# DC309A_CLKGen.net
KiCad netlist of a schematic drawn in Altium Designer
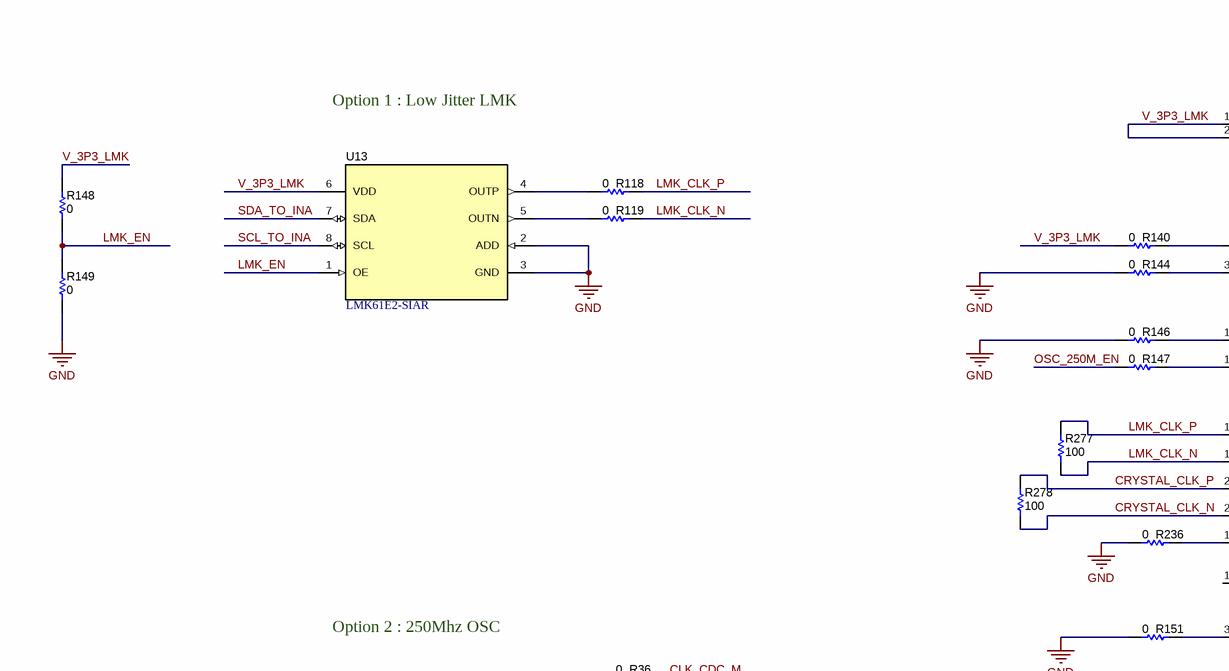
[diagram p0: DC309A_CLKGen.SchDoc, top left]
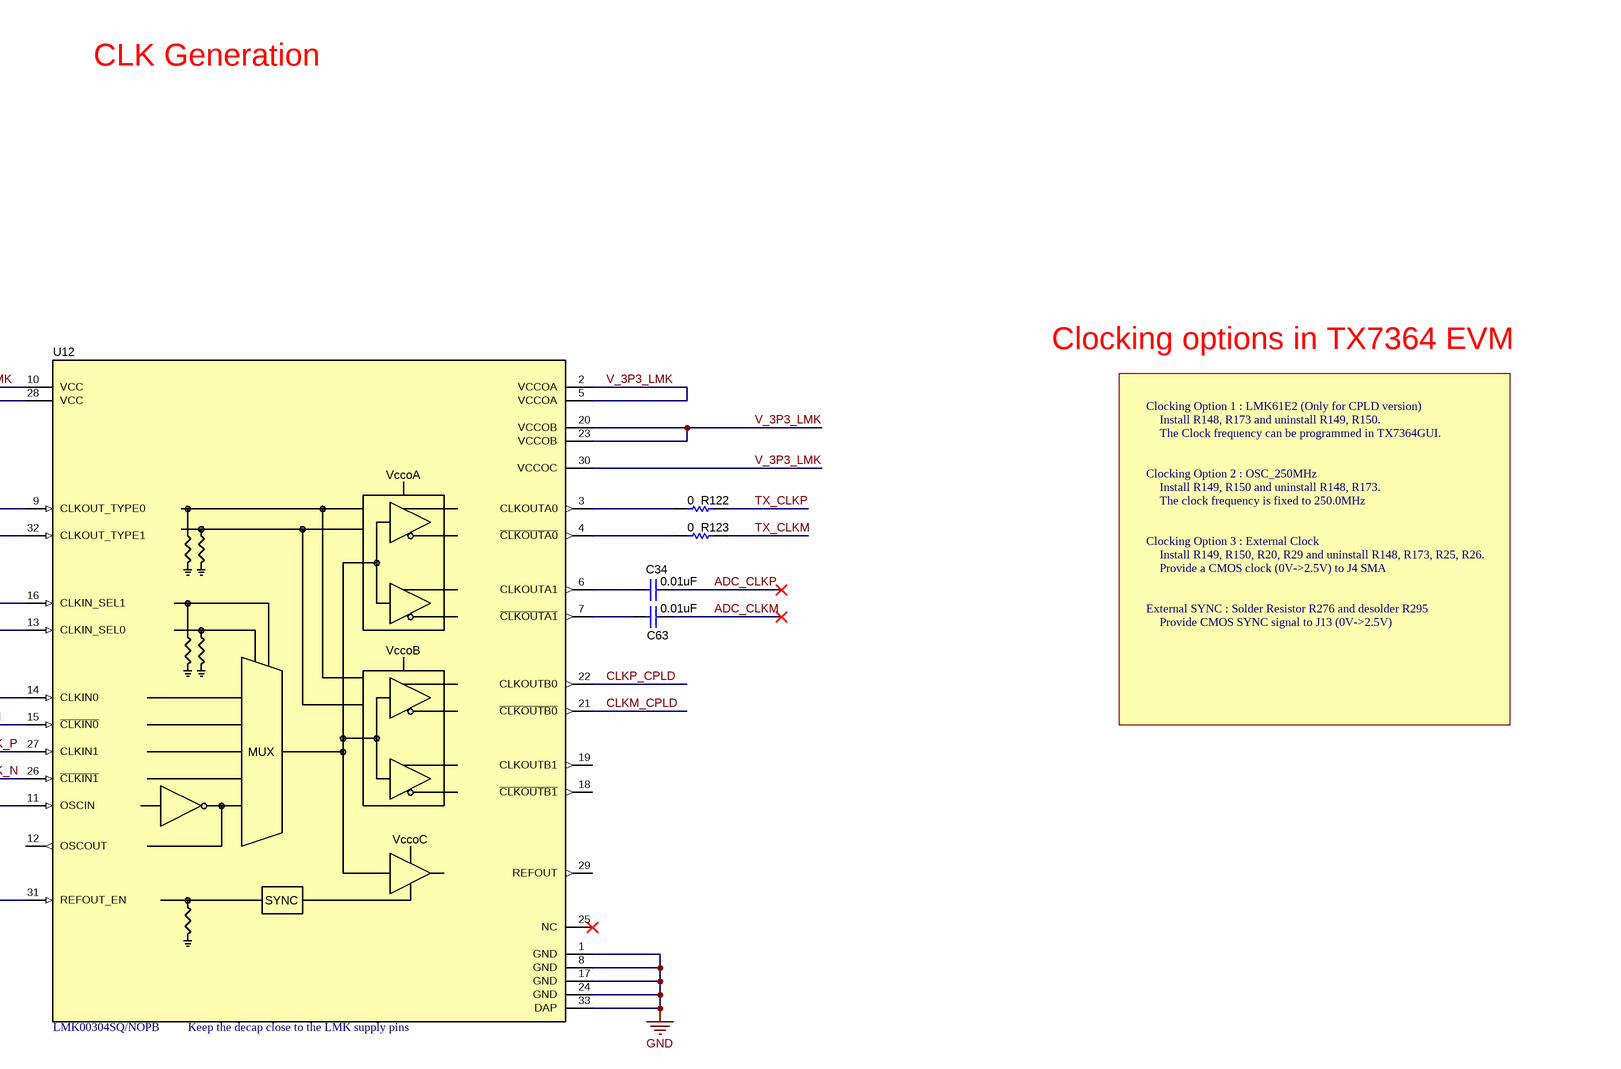
[diagram p1: DC309A_CLKGen.SchDoc, top right]
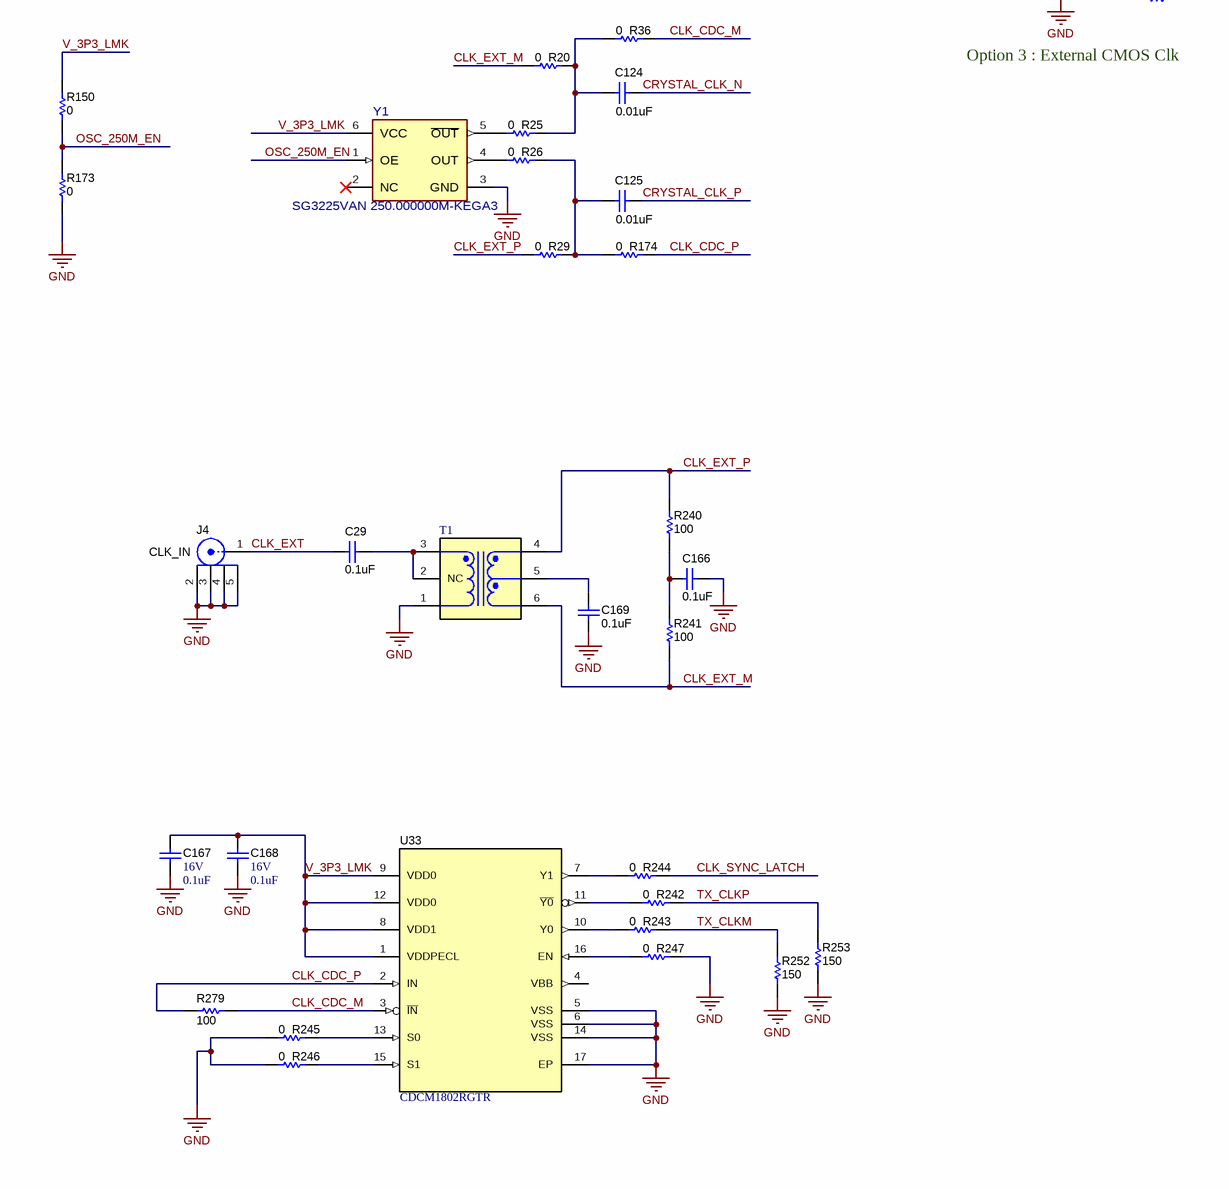
[diagram p2: DC309A_CLKGen.SchDoc, bottom left]
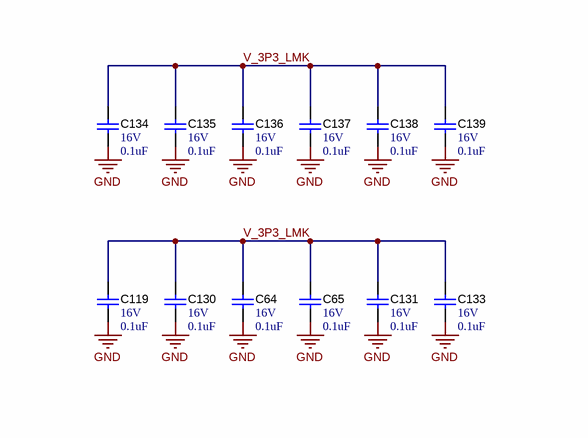
[diagram p3: DC309A_CLKGen.SchDoc, bottom right]

(export (version "E")
  (design (tool "Eeschema 10.0.6"))
  (components
    (comp (ref "C29")
      (value "Capacitor")
      (footprint "0402")
      (description "CAP, CERM, 0.1 uF, 6.3 V, +/- 10%, X5R, 0402")
      (fields
        (field (name "PARTNUMBER") "C1005X5R0J104K050BA")
        (field (name "VALUEDISPLAYED") "0.1uF")
        (field (name "MANUFACTURER") "TDK")
        (field (name "PUBLISHER") "Texas Instruments")
      )
      (libsource (lib "Altium Vault - TI") (part "Capacitor"))
    )
    (comp (ref "C34")
      (value "520L103KT16T")
      (footprint "0402_065")
      (description "CAP, CERM, 0.01 uF, 16 V, +/- 10%, X7R, 0402")
      (fields
        (field (name "MANUFACTURER") "AT Ceramics")
        (field (name "VALUEDISPLAYED") "0.01uF")
        (field (name "PUBLISHER") "Texas Instruments")
      )
      (libsource (lib "Altium Vault - TI") (part "CMP-0006210-2"))
    )
    (comp (ref "C63")
      (value "520L103KT16T")
      (footprint "0402_065")
      (description "CAP, CERM, 0.01 uF, 16 V, +/- 10%, X7R, 0402")
      (fields
        (field (name "MANUFACTURER") "AT Ceramics")
        (field (name "VALUEDISPLAYED") "0.01uF")
        (field (name "PUBLISHER") "Texas Instruments")
      )
      (libsource (lib "Altium Vault - TI") (part "CMP-0006210-2"))
    )
    (comp (ref "C64")
      (value "0402YC104KAT2A")
      (footprint "0402")
      (description "CAP, CERM, 0.1 uF, 16 V, +/- 10%, X7R, 0402")
      (fields
        (field (name "MANUFACTURER") "AVX")
        (field (name "VDC_V") "16V")
        (field (name "VALUEDISPLAYED") "0.1uF")
        (field (name "PUBLISHER") "Texas Instruments")
      )
      (libsource (lib "Altium Vault - TI") (part "Capacitor"))
    )
    (comp (ref "C65")
      (value "0402YC104KAT2A")
      (footprint "0402")
      (description "CAP, CERM, 0.1 uF, 16 V, +/- 10%, X7R, 0402")
      (fields
        (field (name "MANUFACTURER") "AVX")
        (field (name "VDC_V") "16V")
        (field (name "VALUEDISPLAYED") "0.1uF")
        (field (name "PUBLISHER") "Texas Instruments")
      )
      (libsource (lib "Altium Vault - TI") (part "Capacitor"))
    )
    (comp (ref "C119")
      (value "0402YC104KAT2A")
      (footprint "0402")
      (description "CAP, CERM, 0.1 uF, 16 V, +/- 10%, X7R, 0402")
      (fields
        (field (name "MANUFACTURER") "AVX")
        (field (name "VDC_V") "16V")
        (field (name "VALUEDISPLAYED") "0.1uF")
        (field (name "PUBLISHER") "Texas Instruments")
      )
      (libsource (lib "Altium Vault - TI") (part "Capacitor"))
    )
    (comp (ref "C124")
      (value "520L103KT16T")
      (footprint "0402_065")
      (description "CAP, CERM, 0.01 uF, 16 V, +/- 10%, X7R, 0402")
      (fields
        (field (name "MANUFACTURER") "AT Ceramics")
        (field (name "VALUEDISPLAYED") "0.01uF")
        (field (name "PUBLISHER") "Texas Instruments")
      )
      (libsource (lib "Altium Vault - TI") (part "CMP-0006210-2"))
    )
    (comp (ref "C125")
      (value "520L103KT16T")
      (footprint "0402_065")
      (description "CAP, CERM, 0.01 uF, 16 V, +/- 10%, X7R, 0402")
      (fields
        (field (name "MANUFACTURER") "AT Ceramics")
        (field (name "VALUEDISPLAYED") "0.01uF")
        (field (name "PUBLISHER") "Texas Instruments")
      )
      (libsource (lib "Altium Vault - TI") (part "CMP-0006210-2"))
    )
    (comp (ref "C130")
      (value "0402YC104KAT2A")
      (footprint "0402")
      (description "CAP, CERM, 0.1 uF, 16 V, +/- 10%, X7R, 0402")
      (fields
        (field (name "MANUFACTURER") "AVX")
        (field (name "VDC_V") "16V")
        (field (name "VALUEDISPLAYED") "0.1uF")
        (field (name "PUBLISHER") "Texas Instruments")
      )
      (libsource (lib "Altium Vault - TI") (part "Capacitor"))
    )
    (comp (ref "C131")
      (value "0402YC104KAT2A")
      (footprint "0402")
      (description "CAP, CERM, 0.1 uF, 16 V, +/- 10%, X7R, 0402")
      (fields
        (field (name "MANUFACTURER") "AVX")
        (field (name "VDC_V") "16V")
        (field (name "VALUEDISPLAYED") "0.1uF")
        (field (name "PUBLISHER") "Texas Instruments")
      )
      (libsource (lib "Altium Vault - TI") (part "Capacitor"))
    )
    (comp (ref "C133")
      (value "0402YC104KAT2A")
      (footprint "0402")
      (description "CAP, CERM, 0.1 uF, 16 V, +/- 10%, X7R, 0402")
      (fields
        (field (name "MANUFACTURER") "AVX")
        (field (name "VDC_V") "16V")
        (field (name "VALUEDISPLAYED") "0.1uF")
        (field (name "PUBLISHER") "Texas Instruments")
      )
      (libsource (lib "Altium Vault - TI") (part "Capacitor"))
    )
    (comp (ref "C134")
      (value "0402YC104KAT2A")
      (footprint "0402")
      (description "CAP, CERM, 0.1 uF, 16 V, +/- 10%, X7R, 0402")
      (fields
        (field (name "MANUFACTURER") "AVX")
        (field (name "VDC_V") "16V")
        (field (name "VALUEDISPLAYED") "0.1uF")
        (field (name "PUBLISHER") "Texas Instruments")
      )
      (libsource (lib "Altium Vault - TI") (part "Capacitor"))
    )
    (comp (ref "C135")
      (value "0402YC104KAT2A")
      (footprint "0402")
      (description "CAP, CERM, 0.1 uF, 16 V, +/- 10%, X7R, 0402")
      (fields
        (field (name "MANUFACTURER") "AVX")
        (field (name "VDC_V") "16V")
        (field (name "VALUEDISPLAYED") "0.1uF")
        (field (name "PUBLISHER") "Texas Instruments")
      )
      (libsource (lib "Altium Vault - TI") (part "Capacitor"))
    )
    (comp (ref "C136")
      (value "0402YC104KAT2A")
      (footprint "0402")
      (description "CAP, CERM, 0.1 uF, 16 V, +/- 10%, X7R, 0402")
      (fields
        (field (name "MANUFACTURER") "AVX")
        (field (name "VDC_V") "16V")
        (field (name "VALUEDISPLAYED") "0.1uF")
        (field (name "PUBLISHER") "Texas Instruments")
      )
      (libsource (lib "Altium Vault - TI") (part "Capacitor"))
    )
    (comp (ref "C137")
      (value "0402YC104KAT2A")
      (footprint "0402")
      (description "CAP, CERM, 0.1 uF, 16 V, +/- 10%, X7R, 0402")
      (fields
        (field (name "MANUFACTURER") "AVX")
        (field (name "VDC_V") "16V")
        (field (name "VALUEDISPLAYED") "0.1uF")
        (field (name "PUBLISHER") "Texas Instruments")
      )
      (libsource (lib "Altium Vault - TI") (part "Capacitor"))
    )
    (comp (ref "C138")
      (value "0402YC104KAT2A")
      (footprint "0402")
      (description "CAP, CERM, 0.1 uF, 16 V, +/- 10%, X7R, 0402")
      (fields
        (field (name "MANUFACTURER") "AVX")
        (field (name "VDC_V") "16V")
        (field (name "VALUEDISPLAYED") "0.1uF")
        (field (name "PUBLISHER") "Texas Instruments")
      )
      (libsource (lib "Altium Vault - TI") (part "Capacitor"))
    )
    (comp (ref "C139")
      (value "0402YC104KAT2A")
      (footprint "0402")
      (description "CAP, CERM, 0.1 uF, 16 V, +/- 10%, X7R, 0402")
      (fields
        (field (name "MANUFACTURER") "AVX")
        (field (name "VDC_V") "16V")
        (field (name "VALUEDISPLAYED") "0.1uF")
        (field (name "PUBLISHER") "Texas Instruments")
      )
      (libsource (lib "Altium Vault - TI") (part "Capacitor"))
    )
    (comp (ref "C166")
      (value "Capacitor")
      (footprint "0402")
      (description "CAP, CERM, 0.1 uF, 6.3 V, +/- 10%, X5R, 0402")
      (fields
        (field (name "PARTNUMBER") "C1005X5R0J104K050BA")
        (field (name "VALUEDISPLAYED") "0.1uF")
        (field (name "MANUFACTURER") "TDK")
        (field (name "PUBLISHER") "Texas Instruments")
      )
      (libsource (lib "Altium Vault - TI") (part "Capacitor"))
    )
    (comp (ref "C167")
      (value "0402YC104KAT2A")
      (footprint "0402")
      (description "CAP, CERM, 0.1 uF, 16 V, +/- 10%, X7R, 0402")
      (fields
        (field (name "MANUFACTURER") "AVX")
        (field (name "VDC_V") "16V")
        (field (name "VALUEDISPLAYED") "0.1uF")
        (field (name "PUBLISHER") "Texas Instruments")
      )
      (libsource (lib "Altium Vault - TI") (part "Capacitor"))
    )
    (comp (ref "C168")
      (value "0402YC104KAT2A")
      (footprint "0402")
      (description "CAP, CERM, 0.1 uF, 16 V, +/- 10%, X7R, 0402")
      (fields
        (field (name "MANUFACTURER") "AVX")
        (field (name "VDC_V") "16V")
        (field (name "VALUEDISPLAYED") "0.1uF")
        (field (name "PUBLISHER") "Texas Instruments")
      )
      (libsource (lib "Altium Vault - TI") (part "Capacitor"))
    )
    (comp (ref "C169")
      (value "Capacitor")
      (footprint "0402")
      (description "CAP, CERM, 0.1 uF, 6.3 V, +/- 10%, X5R, 0402")
      (fields
        (field (name "PARTNUMBER") "C1005X5R0J104K050BA")
        (field (name "VALUEDISPLAYED") "0.1uF")
        (field (name "MANUFACTURER") "TDK")
        (field (name "PUBLISHER") "Texas Instruments")
      )
      (libsource (lib "Altium Vault - TI") (part "Capacitor"))
    )
    (comp (ref "J4")
      (value "901-144-8RFX")
      (footprint "AMPHENOL_901-144-8RFX")
      (description "SMA Straight Jack, Gold, 50 Ohm, TH")
      (fields (field (name "MANUFACTURER") "Amphenol RF") (field (name "PUBLISHER") "Texas Instruments"))
      (libsource (lib "Altium Vault - TI") (part "SMA_Contact1_GND2345"))
    )
    (comp (ref "R20")
      (value "Resistor")
      (footprint "0402")
      (description "RES, 0, 5%, 0.1 W, AEC-Q200 Grade 0, 0402")
      (fields
        (field (name "PARTNUMBER") "ERJ-2GE0R00X")
        (field (name "MANUFACTURER") "Panasonic")
        (field (name "RES_OHM") "0")
      )
      (libsource (lib "Altium Vault - TI") (part "CMP-0026992-3"))
    )
    (comp (ref "R25")
      (value "Resistor")
      (footprint "0402")
      (description "RES, 0, 5%, 0.1 W, AEC-Q200 Grade 0, 0402")
      (fields
        (field (name "PARTNUMBER") "ERJ-2GE0R00X")
        (field (name "MANUFACTURER") "Panasonic")
        (field (name "RES_OHM") "0")
      )
      (libsource (lib "Altium Vault - TI") (part "CMP-0026992-3"))
    )
    (comp (ref "R26")
      (value "Resistor")
      (footprint "0402")
      (description "RES, 0, 5%, 0.1 W, AEC-Q200 Grade 0, 0402")
      (fields
        (field (name "PARTNUMBER") "ERJ-2GE0R00X")
        (field (name "MANUFACTURER") "Panasonic")
        (field (name "RES_OHM") "0")
      )
      (libsource (lib "Altium Vault - TI") (part "CMP-0026992-3"))
    )
    (comp (ref "R29")
      (value "Resistor")
      (footprint "0402")
      (description "RES, 0, 5%, 0.1 W, AEC-Q200 Grade 0, 0402")
      (fields
        (field (name "PARTNUMBER") "ERJ-2GE0R00X")
        (field (name "MANUFACTURER") "Panasonic")
        (field (name "RES_OHM") "0")
      )
      (libsource (lib "Altium Vault - TI") (part "CMP-0026992-3"))
    )
    (comp (ref "R36")
      (value "Resistor")
      (footprint "0402")
      (description "RES, 0, 5%, 0.1 W, AEC-Q200 Grade 0, 0402")
      (fields
        (field (name "PARTNUMBER") "ERJ-2GE0R00X")
        (field (name "MANUFACTURER") "Panasonic")
        (field (name "RES_OHM") "0")
      )
      (libsource (lib "Altium Vault - TI") (part "CMP-0026992-3"))
    )
    (comp (ref "R118")
      (value "Resistor")
      (footprint "0402")
      (description "RES, 0, 5%, 0.1 W, AEC-Q200 Grade 0, 0402")
      (fields
        (field (name "PARTNUMBER") "ERJ-2GE0R00X")
        (field (name "MANUFACTURER") "Panasonic")
        (field (name "RES_OHM") "0")
      )
      (libsource (lib "Altium Vault - TI") (part "CMP-0026992-3"))
    )
    (comp (ref "R119")
      (value "Resistor")
      (footprint "0402")
      (description "RES, 0, 5%, 0.1 W, AEC-Q200 Grade 0, 0402")
      (fields
        (field (name "PARTNUMBER") "ERJ-2GE0R00X")
        (field (name "MANUFACTURER") "Panasonic")
        (field (name "RES_OHM") "0")
      )
      (libsource (lib "Altium Vault - TI") (part "CMP-0026992-3"))
    )
    (comp (ref "R122")
      (value "Resistor")
      (footprint "0402")
      (description "RES, 0, 5%, 0.1 W, AEC-Q200 Grade 0, 0402")
      (fields
        (field (name "PARTNUMBER") "ERJ-2GE0R00X")
        (field (name "MANUFACTURER") "Panasonic")
        (field (name "RES_OHM") "0")
      )
      (libsource (lib "Altium Vault - TI") (part "CMP-0026992-3"))
    )
    (comp (ref "R123")
      (value "Resistor")
      (footprint "0402")
      (description "RES, 0, 5%, 0.1 W, AEC-Q200 Grade 0, 0402")
      (fields
        (field (name "PARTNUMBER") "ERJ-2GE0R00X")
        (field (name "MANUFACTURER") "Panasonic")
        (field (name "RES_OHM") "0")
      )
      (libsource (lib "Altium Vault - TI") (part "CMP-0026992-3"))
    )
    (comp (ref "R140")
      (value "Resistor")
      (footprint "0402")
      (description "RES, 0, 5%, 0.1 W, AEC-Q200 Grade 0, 0402")
      (fields
        (field (name "PARTNUMBER") "ERJ-2GE0R00X")
        (field (name "MANUFACTURER") "Panasonic")
        (field (name "RES_OHM") "0")
      )
      (libsource (lib "Altium Vault - TI") (part "CMP-0026992-3"))
    )
    (comp (ref "R144")
      (value "Resistor")
      (footprint "0402")
      (description "RES, 0, 5%, 0.1 W, AEC-Q200 Grade 0, 0402")
      (fields
        (field (name "PARTNUMBER") "ERJ-2GE0R00X")
        (field (name "MANUFACTURER") "Panasonic")
        (field (name "RES_OHM") "0")
      )
      (libsource (lib "Altium Vault - TI") (part "CMP-0026992-3"))
    )
    (comp (ref "R146")
      (value "Resistor")
      (footprint "0402")
      (description "RES, 0, 5%, 0.1 W, AEC-Q200 Grade 0, 0402")
      (fields
        (field (name "PARTNUMBER") "ERJ-2GE0R00X")
        (field (name "MANUFACTURER") "Panasonic")
        (field (name "RES_OHM") "0")
      )
      (libsource (lib "Altium Vault - TI") (part "CMP-0026992-3"))
    )
    (comp (ref "R147")
      (value "Resistor")
      (footprint "0402")
      (description "RES, 0, 5%, 0.1 W, AEC-Q200 Grade 0, 0402")
      (fields
        (field (name "PARTNUMBER") "ERJ-2GE0R00X")
        (field (name "MANUFACTURER") "Panasonic")
        (field (name "RES_OHM") "0")
      )
      (libsource (lib "Altium Vault - TI") (part "CMP-0026992-3"))
    )
    (comp (ref "R148")
      (value "Resistor")
      (footprint "0402")
      (description "RES, 0, 5%, 0.1 W, AEC-Q200 Grade 0, 0402")
      (fields
        (field (name "PARTNUMBER") "ERJ-2GE0R00X")
        (field (name "MANUFACTURER") "Panasonic")
        (field (name "RES_OHM") "0")
      )
      (libsource (lib "Altium Vault - TI") (part "CMP-0026992-3"))
    )
    (comp (ref "R149")
      (value "Resistor")
      (footprint "0402")
      (description "RES, 0, 5%, 0.1 W, AEC-Q200 Grade 0, 0402")
      (fields
        (field (name "PARTNUMBER") "ERJ-2GE0R00X")
        (field (name "MANUFACTURER") "Panasonic")
        (field (name "RES_OHM") "0")
      )
      (libsource (lib "Altium Vault - TI") (part "CMP-0026992-3"))
    )
    (comp (ref "R150")
      (value "Resistor")
      (footprint "0402")
      (description "RES, 0, 5%, 0.1 W, AEC-Q200 Grade 0, 0402")
      (fields
        (field (name "PARTNUMBER") "ERJ-2GE0R00X")
        (field (name "MANUFACTURER") "Panasonic")
        (field (name "RES_OHM") "0")
      )
      (libsource (lib "Altium Vault - TI") (part "CMP-0026992-3"))
    )
    (comp (ref "R151")
      (value "Resistor")
      (footprint "0402")
      (description "RES, 0, 5%, 0.1 W, AEC-Q200 Grade 0, 0402")
      (fields
        (field (name "PARTNUMBER") "ERJ-2GE0R00X")
        (field (name "MANUFACTURER") "Panasonic")
        (field (name "RES_OHM") "0")
      )
      (libsource (lib "Altium Vault - TI") (part "CMP-0026992-3"))
    )
    (comp (ref "R173")
      (value "Resistor")
      (footprint "0402")
      (description "RES, 0, 5%, 0.1 W, AEC-Q200 Grade 0, 0402")
      (fields
        (field (name "PARTNUMBER") "ERJ-2GE0R00X")
        (field (name "MANUFACTURER") "Panasonic")
        (field (name "RES_OHM") "0")
      )
      (libsource (lib "Altium Vault - TI") (part "CMP-0026992-3"))
    )
    (comp (ref "R174")
      (value "Resistor")
      (footprint "0402")
      (description "RES, 0, 5%, 0.1 W, AEC-Q200 Grade 0, 0402")
      (fields
        (field (name "PARTNUMBER") "ERJ-2GE0R00X")
        (field (name "MANUFACTURER") "Panasonic")
        (field (name "RES_OHM") "0")
      )
      (libsource (lib "Altium Vault - TI") (part "CMP-0026992-3"))
    )
    (comp (ref "R236")
      (value "Resistor")
      (footprint "0402")
      (description "RES, 0, 5%, 0.1 W, AEC-Q200 Grade 0, 0402")
      (fields
        (field (name "PARTNUMBER") "ERJ-2GE0R00X")
        (field (name "MANUFACTURER") "Panasonic")
        (field (name "RES_OHM") "0")
      )
      (libsource (lib "Altium Vault - TI") (part "CMP-0026992-3"))
    )
    (comp (ref "R240")
      (value "Resistor")
      (footprint "0402")
      (description "RES, 100, 5%, 0.1 W, AEC-Q200 Grade 0, 0402")
      (fields
        (field (name "PARTNUMBER") "ERJ-2GEJ101X")
        (field (name "VALUEDISPLAYED") "100")
        (field (name "MANUFACTURER") "Panasonic")
        (field (name "PUBLISHER") "Texas Instruments")
      )
      (libsource (lib "Altium Vault - TI") (part "Resistor"))
    )
    (comp (ref "R241")
      (value "Resistor")
      (footprint "0402")
      (description "RES, 100, 5%, 0.1 W, AEC-Q200 Grade 0, 0402")
      (fields
        (field (name "PARTNUMBER") "ERJ-2GEJ101X")
        (field (name "VALUEDISPLAYED") "100")
        (field (name "MANUFACTURER") "Panasonic")
        (field (name "PUBLISHER") "Texas Instruments")
      )
      (libsource (lib "Altium Vault - TI") (part "Resistor"))
    )
    (comp (ref "R242")
      (value "Resistor")
      (footprint "0402")
      (description "RES, 0, 5%, 0.1 W, AEC-Q200 Grade 0, 0402")
      (fields
        (field (name "PARTNUMBER") "ERJ-2GE0R00X")
        (field (name "MANUFACTURER") "Panasonic")
        (field (name "RES_OHM") "0")
      )
      (libsource (lib "Altium Vault - TI") (part "CMP-0026992-3"))
    )
    (comp (ref "R243")
      (value "Resistor")
      (footprint "0402")
      (description "RES, 0, 5%, 0.1 W, AEC-Q200 Grade 0, 0402")
      (fields
        (field (name "PARTNUMBER") "ERJ-2GE0R00X")
        (field (name "MANUFACTURER") "Panasonic")
        (field (name "RES_OHM") "0")
      )
      (libsource (lib "Altium Vault - TI") (part "CMP-0026992-3"))
    )
    (comp (ref "R244")
      (value "Resistor")
      (footprint "0402")
      (description "RES, 0, 5%, 0.1 W, AEC-Q200 Grade 0, 0402")
      (fields
        (field (name "PARTNUMBER") "ERJ-2GE0R00X")
        (field (name "MANUFACTURER") "Panasonic")
        (field (name "RES_OHM") "0")
      )
      (libsource (lib "Altium Vault - TI") (part "CMP-0026992-3"))
    )
    (comp (ref "R245")
      (value "Resistor")
      (footprint "0402")
      (description "RES, 0, 5%, 0.1 W, AEC-Q200 Grade 0, 0402")
      (fields
        (field (name "PARTNUMBER") "ERJ-2GE0R00X")
        (field (name "MANUFACTURER") "Panasonic")
        (field (name "RES_OHM") "0")
      )
      (libsource (lib "Altium Vault - TI") (part "CMP-0026992-3"))
    )
    (comp (ref "R246")
      (value "Resistor")
      (footprint "0402")
      (description "RES, 0, 5%, 0.1 W, AEC-Q200 Grade 0, 0402")
      (fields
        (field (name "PARTNUMBER") "ERJ-2GE0R00X")
        (field (name "MANUFACTURER") "Panasonic")
        (field (name "RES_OHM") "0")
      )
      (libsource (lib "Altium Vault - TI") (part "CMP-0026992-3"))
    )
    (comp (ref "R247")
      (value "Resistor")
      (footprint "0402")
      (description "RES, 0, 5%, 0.1 W, AEC-Q200 Grade 0, 0402")
      (fields
        (field (name "PARTNUMBER") "ERJ-2GE0R00X")
        (field (name "MANUFACTURER") "Panasonic")
        (field (name "RES_OHM") "0")
      )
      (libsource (lib "Altium Vault - TI") (part "CMP-0026992-3"))
    )
    (comp (ref "R252")
      (value "RT0603BRD07150RL")
      (footprint "0603")
      (description "RES, 150, 0.1%, 0.1 W, 0603")
      (fields
        (field (name "MANUFACTURER") "Yageo America")
        (field (name "VALUEDISPLAYED") "150")
        (field (name "PUBLISHER") "Texas Instruments")
      )
      (libsource (lib "Altium Vault - TI") (part "Resistor"))
    )
    (comp (ref "R253")
      (value "RT0603BRD07150RL")
      (footprint "0603")
      (description "RES, 150, 0.1%, 0.1 W, 0603")
      (fields
        (field (name "MANUFACTURER") "Yageo America")
        (field (name "VALUEDISPLAYED") "150")
        (field (name "PUBLISHER") "Texas Instruments")
      )
      (libsource (lib "Altium Vault - TI") (part "Resistor"))
    )
    (comp (ref "R277")
      (value "Resistor")
      (footprint "0402")
      (description "RES, 100, 5%, 0.1 W, AEC-Q200 Grade 0, 0402")
      (fields
        (field (name "PARTNUMBER") "ERJ-2GEJ101X")
        (field (name "VALUEDISPLAYED") "100")
        (field (name "MANUFACTURER") "Panasonic")
        (field (name "PUBLISHER") "Texas Instruments")
      )
      (libsource (lib "Altium Vault - TI") (part "Resistor"))
    )
    (comp (ref "R278")
      (value "Resistor")
      (footprint "0402")
      (description "RES, 100, 5%, 0.1 W, AEC-Q200 Grade 0, 0402")
      (fields
        (field (name "PARTNUMBER") "ERJ-2GEJ101X")
        (field (name "VALUEDISPLAYED") "100")
        (field (name "MANUFACTURER") "Panasonic")
        (field (name "PUBLISHER") "Texas Instruments")
      )
      (libsource (lib "Altium Vault - TI") (part "Resistor"))
    )
    (comp (ref "R279")
      (value "Resistor")
      (footprint "0402")
      (description "RES, 100, 5%, 0.1 W, AEC-Q200 Grade 0, 0402")
      (fields
        (field (name "PARTNUMBER") "ERJ-2GEJ101X")
        (field (name "VALUEDISPLAYED") "100")
        (field (name "MANUFACTURER") "Panasonic")
        (field (name "PUBLISHER") "Texas Instruments")
      )
      (libsource (lib "Altium Vault - TI") (part "Resistor"))
    )
    (comp (ref "T1")
      (value "MNC_ADT4-1WT+")
      (footprint "MNC_CD542")
      (description "RF Transformer, 50 ohm, 2 to 775 MHz, SMT")
      (fields
        (field (name "PARTNUMBER") "ADT4-1WT+")
        (field (name "MANUFACTURER") "Minicircuits")
        (field (name "PUBLISHER") "Texas Instruments")
      )
      (libsource (lib "Altium Vault - TI") (part "MNC_ADT4-1WT+"))
    )
    (comp (ref "U12")
      (value "LMK00304SQ/NOPB")
      (footprint "RTV0032A")
      (description "3.1-GHz Differential Clock Buffer/Level Translator, RTV0032A (WQFN-32)")
      (fields (field (name "PARTNUMBER") "LMK00304SQ/NOPB") (field (name "MANUFACTURER") "Texas Instruments"))
      (libsource (lib "Altium Vault - TI") (part "LMK00304"))
    )
    (comp (ref "U13")
      (value "LMK61E2-SIAR")
      (footprint "SIA0008B")
      (description "Ultra-Low Jitter Fully Programmable Oscillator, Integrated EEPROM, +/-50ppm, SIA0008B (QFM-8)")
      (fields
        (field (name "PARTNUMBER") "LMK61E2-SIAR")
        (field (name "MANUFACTURER") "Texas Instruments")
        (field (name "ALTERNATE PARTNUMBER") "LMK61E2-SIAT")
        (field (name "PUBLISHER") "Texas Instruments")
      )
      (libsource (lib "Altium Vault - TI") (part "LMK61E2"))
    )
    (comp (ref "U33")
      (value "CDCM1802RGTR")
      (footprint "RGT0016A")
      (description "Clock Buffer w/Programmable Divider, LVPECL I/O + addl LVCMOS output, RGT0016A (VQFN-16)")
      (fields
        (field (name "ALTERNATE PARTNUMBER") "CDCM1802RGTT")
        (field (name "MANUFACTURER") "Texas Instruments")
        (field (name "PARTNUMBER") "CDCM1802RGTR")
        (field (name "PUBLISHER") "Texas Instruments")
      )
      (libsource (lib "Altium Vault - TI") (part "CDCM1802"))
    )
    (comp (ref "Y1")
      (value "SG3225VAN 250.000000M-KEGA3")
      (footprint "FP-SG3225VAN 250.000000M-KEGA3_XTAL_SMD_3MM2_2MM5-MFG")
      (description "XTAL OSC XO 250.0000MHZ LVDS SMD")
      (fields (field (name "MANUFACTURER") "EPSON"))
      (libsource (lib "Altium Vault - TI") (part "SYM-SG3225VAN 250.000000M-KEGA3"))
    )
  )
  (nets
    (net (code "1") (name "/ADC_CLKM") (class "Default")
      (node (ref "C63") (pin "1") (pinfunction "1_1") (pintype "passive+no_connect"))
    )
    (net (code "2") (name "/ADC_CLKP") (class "Default")
      (node (ref "C34") (pin "1") (pinfunction "1_1") (pintype "passive+no_connect"))
    )
    (net (code "3") (name "/CLKM_CPLD") (class "Default")
      (node (ref "U12") (pin "21") (pinfunction "CLKOUTB0_21") (pintype "output"))
    )
    (net (code "4") (name "/CLKP_CPLD") (class "Default")
      (node (ref "U12") (pin "22") (pinfunction "CLKOUTB0_22") (pintype "output"))
    )
    (net (code "5") (name "/CLK_CDC_M") (class "Default")
      (node (ref "R279") (pin "2") (pinfunction "2_2") (pintype "passive"))
      (node (ref "R36") (pin "2") (pinfunction "2_2") (pintype "passive"))
      (node (ref "U33") (pin "3") (pinfunction "IN_3") (pintype "input"))
    )
    (net (code "6") (name "/CLK_CDC_P") (class "Default")
      (node (ref "R174") (pin "2") (pinfunction "2_2") (pintype "passive"))
      (node (ref "R279") (pin "1") (pinfunction "1_1") (pintype "passive"))
      (node (ref "U33") (pin "2") (pinfunction "IN_2") (pintype "input"))
    )
    (net (code "7") (name "/CLK_EXT") (class "Default")
      (node (ref "C29") (pin "1") (pinfunction "1_1") (pintype "passive"))
      (node (ref "J4") (pin "1") (pinfunction "1_1") (pintype "passive"))
    )
    (net (code "8") (name "/CLK_EXT_M") (class "Default")
      (node (ref "R20") (pin "1") (pinfunction "1_1") (pintype "passive"))
      (node (ref "R241") (pin "1") (pinfunction "1_1") (pintype "passive"))
      (node (ref "T1") (pin "6") (pinfunction "6_6") (pintype "power_in"))
    )
    (net (code "9") (name "/CLK_EXT_P") (class "Default")
      (node (ref "R240") (pin "2") (pinfunction "2_2") (pintype "passive"))
      (node (ref "R29") (pin "1") (pinfunction "1_1") (pintype "passive"))
      (node (ref "T1") (pin "4") (pinfunction "4_4") (pintype "power_in"))
    )
    (net (code "10") (name "/CLK_SYNC_LATCH") (class "Default")
      (node (ref "R244") (pin "2") (pinfunction "2_2") (pintype "passive"))
    )
    (net (code "11") (name "/CRYSTAL_CLK_N") (class "Default")
      (node (ref "C124") (pin "1") (pinfunction "1_1") (pintype "passive"))
      (node (ref "R278") (pin "1") (pinfunction "1_1") (pintype "passive"))
      (node (ref "U12") (pin "26") (pinfunction "CLKIN1_26") (pintype "input"))
    )
    (net (code "12") (name "/CRYSTAL_CLK_P") (class "Default")
      (node (ref "C125") (pin "1") (pinfunction "1_1") (pintype "passive"))
      (node (ref "R278") (pin "2") (pinfunction "2_2") (pintype "passive"))
      (node (ref "U12") (pin "27") (pinfunction "CLKIN1_27") (pintype "input"))
    )
    (net (code "13") (name "/LMK_CLK_N") (class "Default")
      (node (ref "R119") (pin "2") (pinfunction "2_2") (pintype "passive"))
      (node (ref "R277") (pin "1") (pinfunction "1_1") (pintype "passive"))
      (node (ref "U12") (pin "15") (pinfunction "CLKIN0_15") (pintype "input"))
    )
    (net (code "14") (name "/LMK_CLK_P") (class "Default")
      (node (ref "R118") (pin "2") (pinfunction "2_2") (pintype "passive"))
      (node (ref "R277") (pin "2") (pinfunction "2_2") (pintype "passive"))
      (node (ref "U12") (pin "14") (pinfunction "CLKIN0_14") (pintype "input"))
    )
    (net (code "15") (name "/LMK_EN") (class "Default")
      (node (ref "R148") (pin "1") (pinfunction "1_1") (pintype "passive"))
      (node (ref "R149") (pin "2") (pinfunction "2_2") (pintype "passive"))
      (node (ref "U13") (pin "1") (pinfunction "OE_1") (pintype "input"))
    )
    (net (code "16") (name "/OSC_250M_EN") (class "Default")
      (node (ref "R147") (pin "1") (pinfunction "1_1") (pintype "passive"))
      (node (ref "R150") (pin "1") (pinfunction "1_1") (pintype "passive"))
      (node (ref "R173") (pin "2") (pinfunction "2_2") (pintype "passive"))
      (node (ref "Y1") (pin "1") (pinfunction "OE_1") (pintype "input"))
    )
    (net (code "17") (name "/SCL_TO_INA") (class "Default")
      (node (ref "U13") (pin "8") (pinfunction "SCL_8") (pintype "bidirectional"))
    )
    (net (code "18") (name "/SDA_TO_INA") (class "Default")
      (node (ref "U13") (pin "7") (pinfunction "SDA_7") (pintype "bidirectional"))
    )
    (net (code "19") (name "/TX_CLKM") (class "Default")
      (node (ref "R123") (pin "2") (pinfunction "2_2") (pintype "passive"))
      (node (ref "R243") (pin "2") (pinfunction "2_2") (pintype "passive"))
      (node (ref "R252") (pin "2") (pinfunction "2_2") (pintype "passive"))
    )
    (net (code "20") (name "/TX_CLKP") (class "Default")
      (node (ref "R122") (pin "2") (pinfunction "2_2") (pintype "passive"))
      (node (ref "R242") (pin "2") (pinfunction "2_2") (pintype "passive"))
      (node (ref "R253") (pin "2") (pinfunction "2_2") (pintype "passive"))
    )
    (net (code "21") (name "/V_3P3_LMK") (class "Default")
      (node (ref "C119") (pin "1") (pinfunction "1_1") (pintype "passive"))
      (node (ref "C130") (pin "1") (pinfunction "1_1") (pintype "passive"))
      (node (ref "C131") (pin "1") (pinfunction "1_1") (pintype "passive"))
      (node (ref "C133") (pin "1") (pinfunction "1_1") (pintype "passive"))
      (node (ref "C134") (pin "1") (pinfunction "1_1") (pintype "passive"))
      (node (ref "C135") (pin "1") (pinfunction "1_1") (pintype "passive"))
      (node (ref "C136") (pin "1") (pinfunction "1_1") (pintype "passive"))
      (node (ref "C137") (pin "1") (pinfunction "1_1") (pintype "passive"))
      (node (ref "C138") (pin "1") (pinfunction "1_1") (pintype "passive"))
      (node (ref "C139") (pin "1") (pinfunction "1_1") (pintype "passive"))
      (node (ref "C167") (pin "1") (pinfunction "1_1") (pintype "passive"))
      (node (ref "C168") (pin "1") (pinfunction "1_1") (pintype "passive"))
      (node (ref "C64") (pin "1") (pinfunction "1_1") (pintype "passive"))
      (node (ref "C65") (pin "1") (pinfunction "1_1") (pintype "passive"))
      (node (ref "R140") (pin "1") (pinfunction "1_1") (pintype "passive"))
      (node (ref "R148") (pin "2") (pinfunction "2_2") (pintype "passive"))
      (node (ref "R150") (pin "2") (pinfunction "2_2") (pintype "passive"))
      (node (ref "U12") (pin "10") (pinfunction "VCC_10") (pintype "power_in"))
      (node (ref "U12") (pin "2") (pinfunction "VCCOA_2") (pintype "power_in"))
      (node (ref "U12") (pin "20") (pinfunction "VCCOB_20") (pintype "power_in"))
      (node (ref "U12") (pin "23") (pinfunction "VCCOB_23") (pintype "power_in"))
      (node (ref "U12") (pin "28") (pinfunction "VCC_28") (pintype "power_in"))
      (node (ref "U12") (pin "30") (pinfunction "VCCOC_30") (pintype "power_in"))
      (node (ref "U12") (pin "5") (pinfunction "VCCOA_5") (pintype "power_in"))
      (node (ref "U13") (pin "6") (pinfunction "VDD_6") (pintype "power_in"))
      (node (ref "U33") (pin "1") (pinfunction "VDDPECL_1") (pintype "power_in"))
      (node (ref "U33") (pin "12") (pinfunction "VDD0_12") (pintype "power_in"))
      (node (ref "U33") (pin "8") (pinfunction "VDD1_8") (pintype "power_in"))
      (node (ref "U33") (pin "9") (pinfunction "VDD0_9") (pintype "power_in"))
      (node (ref "Y1") (pin "6") (pinfunction "VCC_6") (pintype "power_in"))
    )
    (net (code "22") (name "GND") (class "Default")
      (node (ref "C119") (pin "2") (pinfunction "2_2") (pintype "passive"))
      (node (ref "C130") (pin "2") (pinfunction "2_2") (pintype "passive"))
      (node (ref "C131") (pin "2") (pinfunction "2_2") (pintype "passive"))
      (node (ref "C133") (pin "2") (pinfunction "2_2") (pintype "passive"))
      (node (ref "C134") (pin "2") (pinfunction "2_2") (pintype "passive"))
      (node (ref "C135") (pin "2") (pinfunction "2_2") (pintype "passive"))
      (node (ref "C136") (pin "2") (pinfunction "2_2") (pintype "passive"))
      (node (ref "C137") (pin "2") (pinfunction "2_2") (pintype "passive"))
      (node (ref "C138") (pin "2") (pinfunction "2_2") (pintype "passive"))
      (node (ref "C139") (pin "2") (pinfunction "2_2") (pintype "passive"))
      (node (ref "C166") (pin "1") (pinfunction "1_1") (pintype "passive"))
      (node (ref "C167") (pin "2") (pinfunction "2_2") (pintype "passive"))
      (node (ref "C168") (pin "2") (pinfunction "2_2") (pintype "passive"))
      (node (ref "C169") (pin "1") (pinfunction "1_1") (pintype "passive"))
      (node (ref "C64") (pin "2") (pinfunction "2_2") (pintype "passive"))
      (node (ref "C65") (pin "2") (pinfunction "2_2") (pintype "passive"))
      (node (ref "J4") (pin "2") (pinfunction "2_2") (pintype "passive"))
      (node (ref "J4") (pin "3") (pinfunction "3_3") (pintype "passive"))
      (node (ref "J4") (pin "4") (pinfunction "4_4") (pintype "passive"))
      (node (ref "J4") (pin "5") (pinfunction "5_5") (pintype "passive"))
      (node (ref "R144") (pin "1") (pinfunction "1_1") (pintype "passive"))
      (node (ref "R146") (pin "1") (pinfunction "1_1") (pintype "passive"))
      (node (ref "R149") (pin "1") (pinfunction "1_1") (pintype "passive"))
      (node (ref "R151") (pin "1") (pinfunction "1_1") (pintype "passive"))
      (node (ref "R173") (pin "1") (pinfunction "1_1") (pintype "passive"))
      (node (ref "R236") (pin "1") (pinfunction "1_1") (pintype "passive"))
      (node (ref "R245") (pin "1") (pinfunction "1_1") (pintype "passive"))
      (node (ref "R246") (pin "1") (pinfunction "1_1") (pintype "passive"))
      (node (ref "R247") (pin "2") (pinfunction "2_2") (pintype "passive"))
      (node (ref "R252") (pin "1") (pinfunction "1_1") (pintype "passive"))
      (node (ref "R253") (pin "1") (pinfunction "1_1") (pintype "passive"))
      (node (ref "T1") (pin "1") (pinfunction "1_1") (pintype "power_in"))
      (node (ref "U12") (pin "1") (pinfunction "GND_1") (pintype "power_in"))
      (node (ref "U12") (pin "17") (pinfunction "GND_17") (pintype "power_in"))
      (node (ref "U12") (pin "24") (pinfunction "GND_24") (pintype "power_in"))
      (node (ref "U12") (pin "33") (pinfunction "DAP_33") (pintype "power_in"))
      (node (ref "U12") (pin "8") (pinfunction "GND_8") (pintype "power_in"))
      (node (ref "U13") (pin "2") (pinfunction "ADD_2") (pintype "input"))
      (node (ref "U13") (pin "3") (pinfunction "GND_3") (pintype "power_in"))
      (node (ref "U33") (pin "14") (pinfunction "VSS_14") (pintype "power_in"))
      (node (ref "U33") (pin "17") (pinfunction "EP_17") (pintype "power_in"))
      (node (ref "U33") (pin "5") (pinfunction "VSS_5") (pintype "power_in"))
      (node (ref "U33") (pin "6") (pinfunction "VSS_6") (pintype "power_in"))
      (node (ref "Y1") (pin "3") (pinfunction "GND_3") (pintype "power_in"))
    )
    (net (code "23") (name "Net-(C34-Pad2)") (class "Default")
      (node (ref "C34") (pin "2") (pinfunction "2_2") (pintype "passive"))
      (node (ref "U12") (pin "6") (pinfunction "CLKOUTA1_6") (pintype "output"))
    )
    (net (code "24") (name "Net-(C63-Pad2)") (class "Default")
      (node (ref "C63") (pin "2") (pinfunction "2_2") (pintype "passive"))
      (node (ref "U12") (pin "7") (pinfunction "CLKOUTA1_7") (pintype "output"))
    )
    (net (code "25") (name "Net-(C124-Pad2)") (class "Default")
      (node (ref "C124") (pin "2") (pinfunction "2_2") (pintype "passive"))
      (node (ref "R20") (pin "2") (pinfunction "2_2") (pintype "passive"))
      (node (ref "R25") (pin "2") (pinfunction "2_2") (pintype "passive"))
      (node (ref "R36") (pin "1") (pinfunction "1_1") (pintype "passive"))
    )
    (net (code "26") (name "Net-(C125-Pad2)") (class "Default")
      (node (ref "C125") (pin "2") (pinfunction "2_2") (pintype "passive"))
      (node (ref "R174") (pin "1") (pinfunction "1_1") (pintype "passive"))
      (node (ref "R26") (pin "2") (pinfunction "2_2") (pintype "passive"))
      (node (ref "R29") (pin "2") (pinfunction "2_2") (pintype "passive"))
    )
    (net (code "27") (name "Net-(C166-Pad2)") (class "Default")
      (node (ref "C166") (pin "2") (pinfunction "2_2") (pintype "passive"))
      (node (ref "R240") (pin "1") (pinfunction "1_1") (pintype "passive"))
      (node (ref "R241") (pin "2") (pinfunction "2_2") (pintype "passive"))
    )
    (net (code "28") (name "Net-(C169-Pad2)") (class "Default")
      (node (ref "C169") (pin "2") (pinfunction "2_2") (pintype "passive"))
      (node (ref "T1") (pin "5") (pinfunction "5_5") (pintype "power_in"))
    )
    (net (code "29") (name "Net-(R122-Pad1)") (class "Default")
      (node (ref "R122") (pin "1") (pinfunction "1_1") (pintype "passive"))
      (node (ref "U12") (pin "3") (pinfunction "CLKOUTA0_3") (pintype "output"))
    )
    (net (code "30") (name "Net-(R123-Pad1)") (class "Default")
      (node (ref "R123") (pin "1") (pinfunction "1_1") (pintype "passive"))
      (node (ref "U12") (pin "4") (pinfunction "CLKOUTA0_4") (pintype "output"))
    )
    (net (code "31") (name "Net-(R242-Pad1)") (class "Default")
      (node (ref "R242") (pin "1") (pinfunction "1_1") (pintype "passive"))
      (node (ref "U33") (pin "11") (pinfunction "Y0_11") (pintype "output"))
    )
    (net (code "32") (name "Net-(R243-Pad1)") (class "Default")
      (node (ref "R243") (pin "1") (pinfunction "1_1") (pintype "passive"))
      (node (ref "U33") (pin "10") (pinfunction "Y0_10") (pintype "output"))
    )
    (net (code "33") (name "Net-(T1-NC)") (class "Default")
      (node (ref "C29") (pin "2") (pinfunction "2_2") (pintype "passive"))
      (node (ref "T1") (pin "2") (pinfunction "NC_2") (pintype "passive"))
      (node (ref "T1") (pin "3") (pinfunction "3_3") (pintype "power_in"))
    )
    (net (code "34") (name "Net-(U12-CLKIN_SEL0)") (class "Default")
      (node (ref "R147") (pin "2") (pinfunction "2_2") (pintype "passive"))
      (node (ref "U12") (pin "13") (pinfunction "CLKIN_SEL0_13") (pintype "input"))
    )
    (net (code "35") (name "Net-(U12-CLKIN_SEL1)") (class "Default")
      (node (ref "R146") (pin "2") (pinfunction "2_2") (pintype "passive"))
      (node (ref "U12") (pin "16") (pinfunction "CLKIN_SEL1_16") (pintype "input"))
    )
    (net (code "36") (name "Net-(U12-CLKOUT_TYPE0)") (class "Default")
      (node (ref "R140") (pin "2") (pinfunction "2_2") (pintype "passive"))
      (node (ref "U12") (pin "9") (pinfunction "CLKOUT_TYPE0_9") (pintype "input"))
    )
    (net (code "37") (name "Net-(U12-CLKOUT_TYPE1)") (class "Default")
      (node (ref "R144") (pin "2") (pinfunction "2_2") (pintype "passive"))
      (node (ref "U12") (pin "32") (pinfunction "CLKOUT_TYPE1_32") (pintype "input"))
    )
    (net (code "38") (name "Net-(U12-OSCIN)") (class "Default")
      (node (ref "R236") (pin "2") (pinfunction "2_2") (pintype "passive"))
      (node (ref "U12") (pin "11") (pinfunction "OSCIN_11") (pintype "input"))
    )
    (net (code "39") (name "Net-(U12-REFOUT_EN)") (class "Default")
      (node (ref "R151") (pin "2") (pinfunction "2_2") (pintype "passive"))
      (node (ref "U12") (pin "31") (pinfunction "REFOUT_EN_31") (pintype "input"))
    )
    (net (code "40") (name "Net-(U13-OUTN)") (class "Default")
      (node (ref "R119") (pin "1") (pinfunction "1_1") (pintype "passive"))
      (node (ref "U13") (pin "5") (pinfunction "OUTN_5") (pintype "output"))
    )
    (net (code "41") (name "Net-(U13-OUTP)") (class "Default")
      (node (ref "R118") (pin "1") (pinfunction "1_1") (pintype "passive"))
      (node (ref "U13") (pin "4") (pinfunction "OUTP_4") (pintype "output"))
    )
    (net (code "42") (name "Net-(U33-EN)") (class "Default")
      (node (ref "R247") (pin "1") (pinfunction "1_1") (pintype "passive"))
      (node (ref "U33") (pin "16") (pinfunction "EN_16") (pintype "input"))
    )
    (net (code "43") (name "Net-(U33-S0)") (class "Default")
      (node (ref "R245") (pin "2") (pinfunction "2_2") (pintype "passive"))
      (node (ref "U33") (pin "13") (pinfunction "S0_13") (pintype "input"))
    )
    (net (code "44") (name "Net-(U33-S1)") (class "Default")
      (node (ref "R246") (pin "2") (pinfunction "2_2") (pintype "passive"))
      (node (ref "U33") (pin "15") (pinfunction "S1_15") (pintype "input"))
    )
    (net (code "45") (name "Net-(U33-Y1)") (class "Default")
      (node (ref "R244") (pin "1") (pinfunction "1_1") (pintype "passive"))
      (node (ref "U33") (pin "7") (pinfunction "Y1_7") (pintype "output"))
    )
    (net (code "46") (name "Net-(Y1-OUT)") (class "Default")
      (node (ref "R26") (pin "1") (pinfunction "1_1") (pintype "passive"))
      (node (ref "Y1") (pin "4") (pinfunction "OUT_4") (pintype "output"))
    )
    (net (code "47") (name "Net-(Y1-~{OUT})") (class "Default")
      (node (ref "R25") (pin "1") (pinfunction "1_1") (pintype "passive"))
      (node (ref "Y1") (pin "5") (pinfunction "~{OUT}_5") (pintype "output"))
    )
    (net (code "48") (name "unconnected-(U12-CLKOUTB1-Pad18)") (class "Default")
      (node (ref "U12") (pin "18") (pinfunction "CLKOUTB1_18") (pintype "output"))
    )
    (net (code "49") (name "unconnected-(U12-CLKOUTB1-Pad19)") (class "Default")
      (node (ref "U12") (pin "19") (pinfunction "CLKOUTB1_19") (pintype "output"))
    )
    (net (code "50") (name "unconnected-(U12-NC-Pad25)") (class "Default")
      (node (ref "U12") (pin "25") (pinfunction "NC_25") (pintype "passive+no_connect"))
    )
    (net (code "51") (name "unconnected-(U12-OSCOUT-Pad12)") (class "Default")
      (node (ref "U12") (pin "12") (pinfunction "OSCOUT_12") (pintype "output"))
    )
    (net (code "52") (name "unconnected-(U12-REFOUT-Pad29)") (class "Default")
      (node (ref "U12") (pin "29") (pinfunction "REFOUT_29") (pintype "output"))
    )
    (net (code "53") (name "unconnected-(U33-VBB-Pad4)") (class "Default")
      (node (ref "U33") (pin "4") (pinfunction "VBB_4") (pintype "output"))
    )
    (net (code "54") (name "unconnected-(Y1-NC-Pad2)") (class "Default")
      (node (ref "Y1") (pin "2") (pinfunction "NC_2") (pintype "passive+no_connect"))
    )
  )
)
